# SCH_555-circuit_2025-10-18.net
KiCad netlist of a schematic drawn in EasyEDA
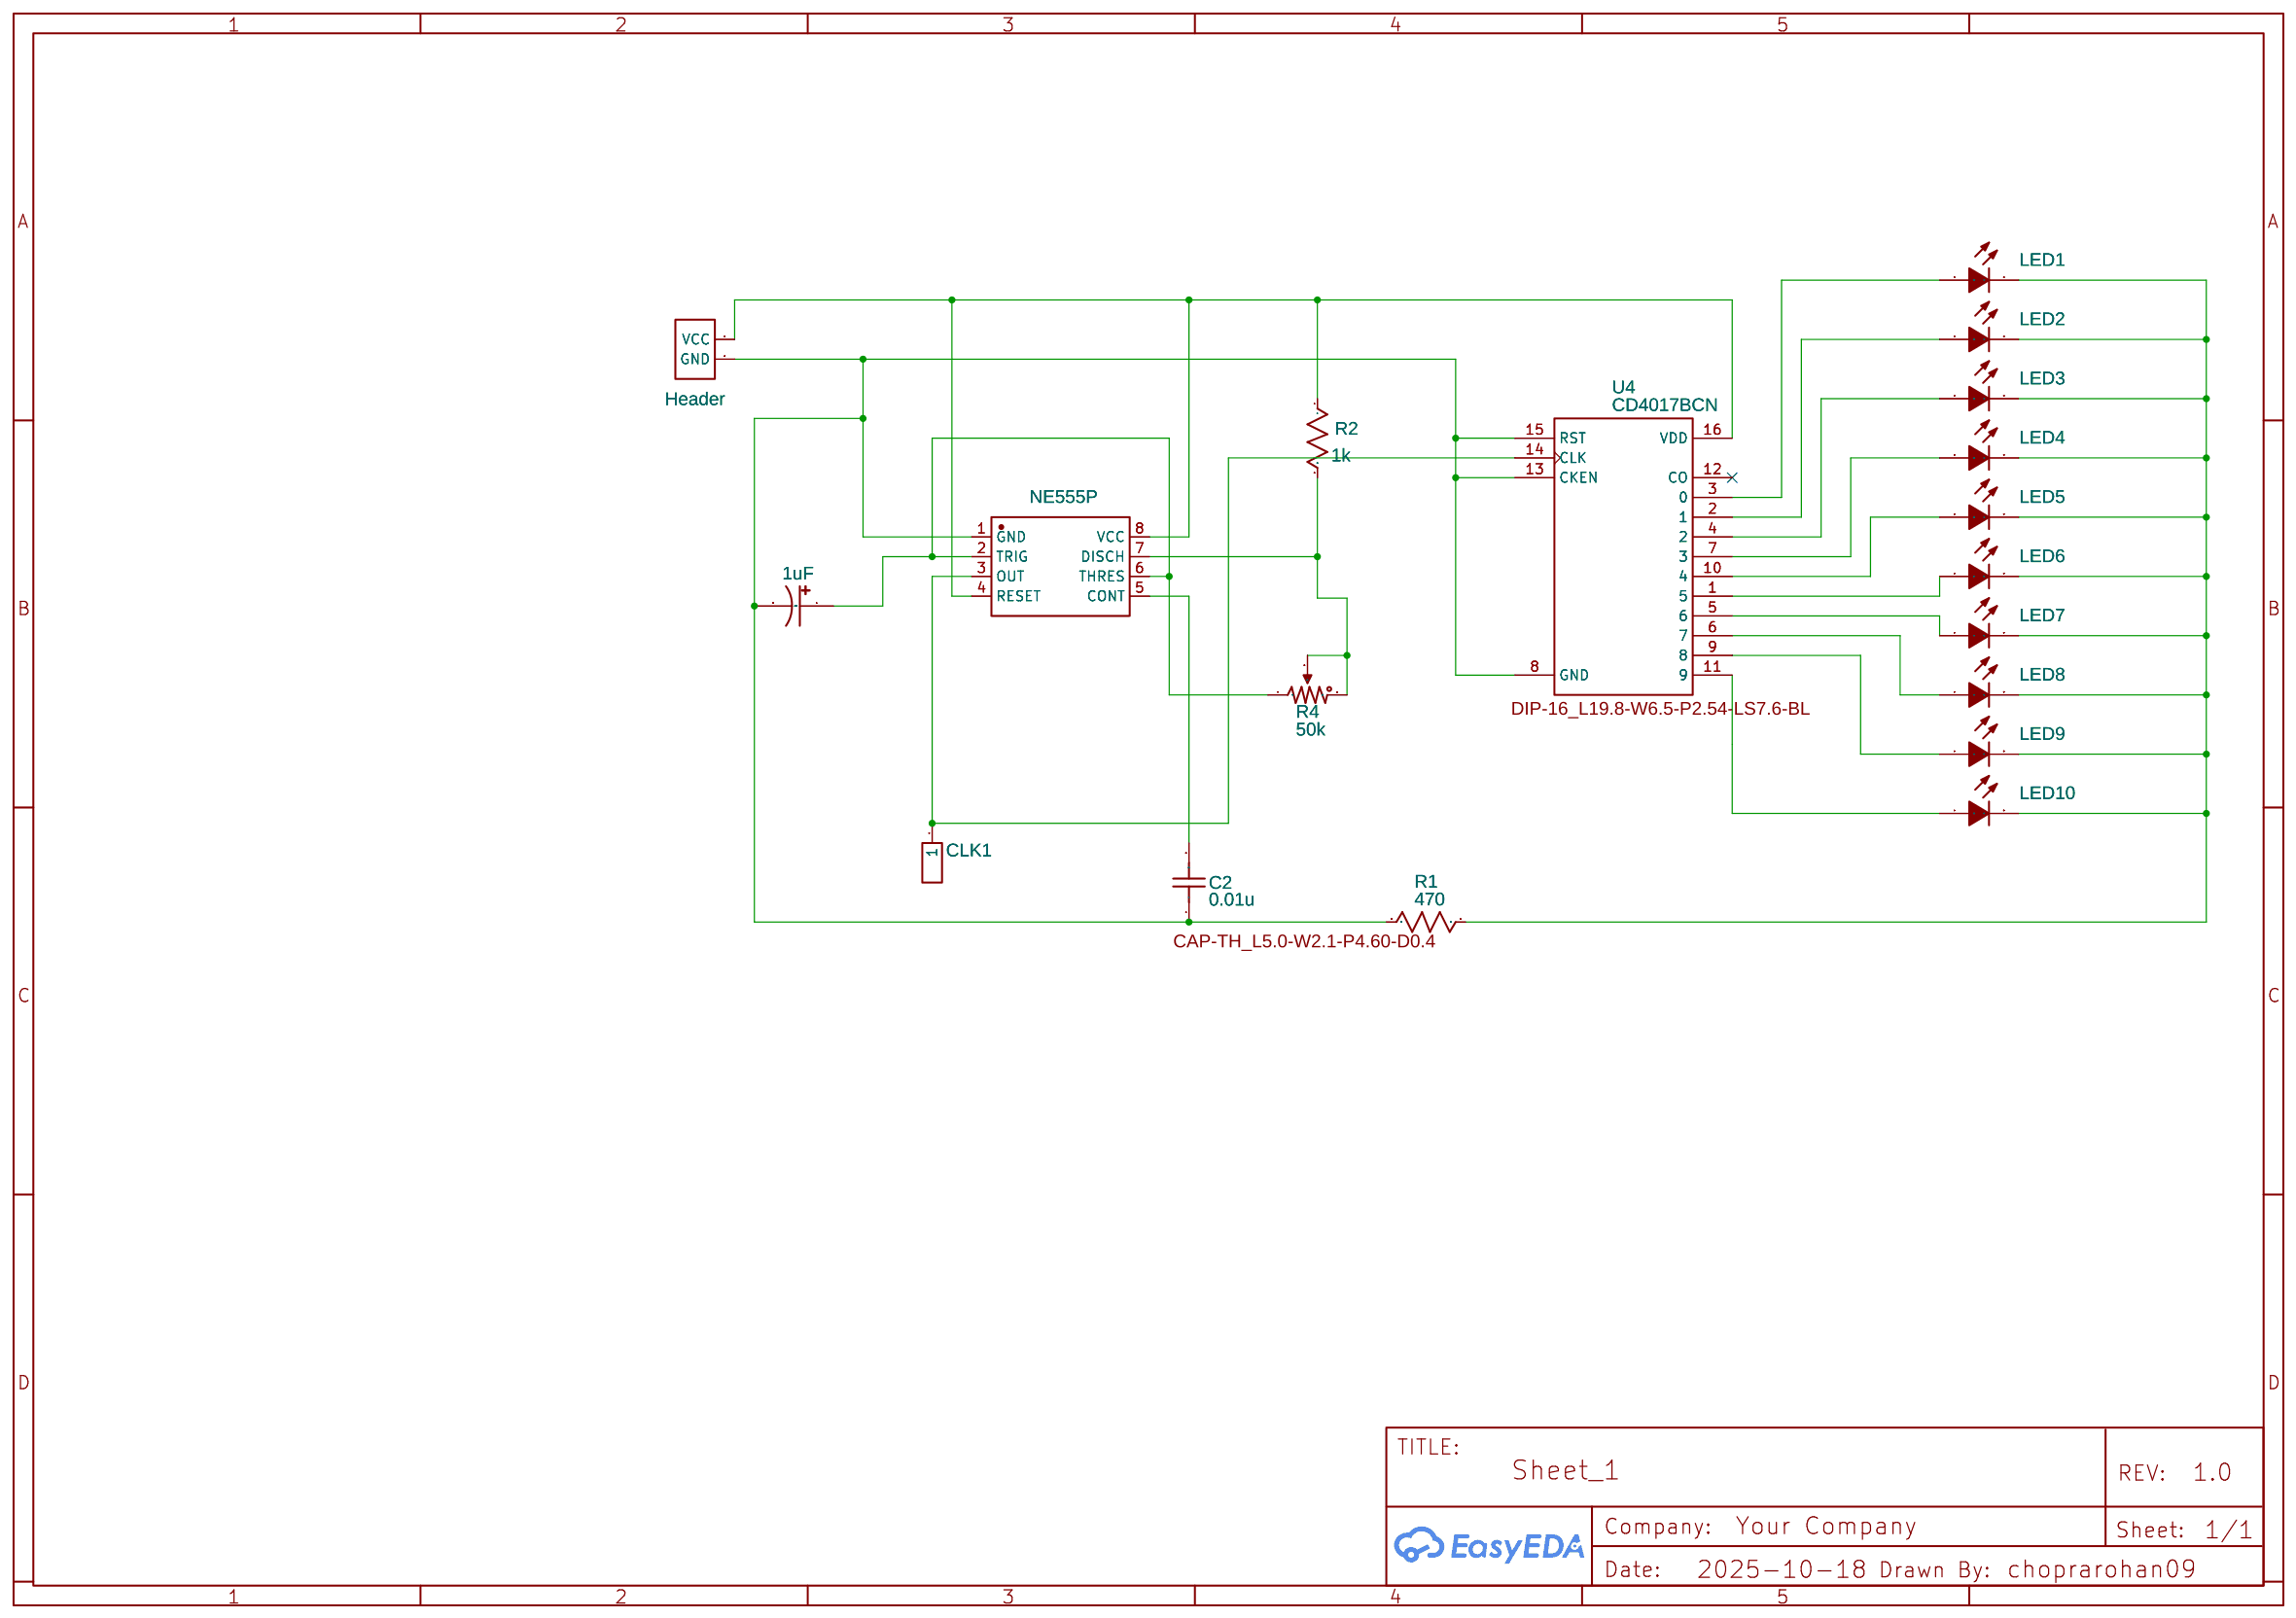
[diagram p0: schematic sheet]

(export (version "E")
  (design (tool "Eeschema 10.0.6"))
  (components
    (comp (ref "C1")
      (value "1uF")
      (fields (field (name "Manufacturer Part") "UVZ1H010MDD") (field (name "Manufacturer") "Nichicon(尼吉康)"))
      (libsource (lib "") (part "UVZ1H010MDD"))
    )
    (comp (ref "C2") (value "0.01u") (libsource (lib "") (part "C_0603_US")))
    (comp (ref "CLK1")
      (value "C81276")
      (fields
        (field (name "Manufacturer Part") "2.54-1*1P针")
        (field (name "Manufacturer") "BOOMELE(Boom Precision Elec)")
      )
      (libsource (lib "") (part "Header-Male-2.54_1x1"))
    )
    (comp (ref "H1") (value "Header") (libsource (lib "") (part "HEADER-FEMALE-2.54_1X2")))
    (comp (ref "LED1") (value "LED_5MM") (libsource (lib "") (part "LED_5MM")))
    (comp (ref "LED2") (value "LED_5MM") (libsource (lib "") (part "LED_5MM")))
    (comp (ref "LED3") (value "LED_5MM") (libsource (lib "") (part "LED_5MM")))
    (comp (ref "LED4") (value "LED_5MM") (libsource (lib "") (part "LED_5MM")))
    (comp (ref "LED5") (value "LED_5MM") (libsource (lib "") (part "LED_5MM")))
    (comp (ref "LED6") (value "LED_5MM") (libsource (lib "") (part "LED_5MM")))
    (comp (ref "LED7") (value "LED_5MM") (libsource (lib "") (part "LED_5MM")))
    (comp (ref "LED8") (value "LED_5MM") (libsource (lib "") (part "LED_5MM")))
    (comp (ref "LED9") (value "LED_5MM") (libsource (lib "") (part "LED_5MM")))
    (comp (ref "LED10") (value "LED_5MM") (libsource (lib "") (part "LED_5MM")))
    (comp (ref "R1")
      (value "470")
      (fields (field (name "Manufacturer Part") "?"))
      (libsource (lib "") (part "Resistor"))
    )
    (comp (ref "R2")
      (value "1k")
      (fields (field (name "Manufacturer Part") "?"))
      (libsource (lib "") (part "Resistor_1"))
    )
    (comp (ref "R4")
      (value "50k")
      (fields (field (name "Manufacturer Part") "?"))
      (libsource (lib "") (part "Potentiometer"))
    )
    (comp (ref "U2")
      (value "NE555P")
      (fields (field (name "Manufacturer") "TI(德州仪器)"))
      (libsource (lib "") (part "NE555P"))
    )
    (comp (ref "U4") (value "CD4017BCN") (libsource (lib "") (part "CD4017BCN")))
  )
  (nets
    (net (code "1") (name "Net-(H1-GND)") (class "Default")
      (node (ref "C1") (pin "2") (pinfunction "2_2") (pintype "unspecified"))
      (node (ref "C2") (pin "1") (pinfunction "1_1") (pintype "unspecified"))
      (node (ref "H1") (pin "2") (pinfunction "GND_2") (pintype "unspecified"))
      (node (ref "R1") (pin "2") (pinfunction "2_2") (pintype "unspecified"))
      (node (ref "U2") (pin "1") (pinfunction "GND_1") (pintype "unspecified"))
      (node (ref "U4") (pin "13") (pinfunction "CKEN_13") (pintype "unspecified"))
      (node (ref "U4") (pin "15") (pinfunction "RST_15") (pintype "unspecified"))
      (node (ref "U4") (pin "8") (pinfunction "GND_8") (pintype "passive"))
    )
    (net (code "2") (name "Net-(H1-VCC)") (class "Default")
      (node (ref "H1") (pin "1") (pinfunction "VCC_1") (pintype "unspecified"))
      (node (ref "R2") (pin "1") (pinfunction "1_1") (pintype "unspecified"))
      (node (ref "U2") (pin "4") (pinfunction "RESET_4") (pintype "unspecified"))
      (node (ref "U2") (pin "8") (pinfunction "VCC_8") (pintype "unspecified"))
      (node (ref "U4") (pin "16") (pinfunction "VDD_16") (pintype "passive"))
    )
    (net (code "3") (name "Net-(LED1-A)") (class "Default")
      (node (ref "LED1") (pin "1") (pinfunction "A_1") (pintype "input"))
      (node (ref "U4") (pin "3") (pinfunction "0_3") (pintype "output"))
    )
    (net (code "4") (name "Net-(LED1-K)") (class "Default")
      (node (ref "LED1") (pin "2") (pinfunction "K_2") (pintype "input"))
      (node (ref "LED10") (pin "2") (pinfunction "K_2") (pintype "input"))
      (node (ref "LED2") (pin "2") (pinfunction "K_2") (pintype "input"))
      (node (ref "LED3") (pin "2") (pinfunction "K_2") (pintype "input"))
      (node (ref "LED4") (pin "2") (pinfunction "K_2") (pintype "input"))
      (node (ref "LED5") (pin "2") (pinfunction "K_2") (pintype "input"))
      (node (ref "LED6") (pin "2") (pinfunction "K_2") (pintype "input"))
      (node (ref "LED7") (pin "2") (pinfunction "K_2") (pintype "input"))
      (node (ref "LED8") (pin "2") (pinfunction "K_2") (pintype "input"))
      (node (ref "LED9") (pin "2") (pinfunction "K_2") (pintype "input"))
      (node (ref "R1") (pin "1") (pinfunction "1_1") (pintype "unspecified"))
    )
    (net (code "5") (name "Net-(LED2-A)") (class "Default")
      (node (ref "LED2") (pin "1") (pinfunction "A_1") (pintype "input"))
      (node (ref "U4") (pin "2") (pinfunction "1_2") (pintype "output"))
    )
    (net (code "6") (name "Net-(LED3-A)") (class "Default")
      (node (ref "LED3") (pin "1") (pinfunction "A_1") (pintype "input"))
      (node (ref "U4") (pin "4") (pinfunction "2_4") (pintype "output"))
    )
    (net (code "7") (name "Net-(LED4-A)") (class "Default")
      (node (ref "LED4") (pin "1") (pinfunction "A_1") (pintype "input"))
      (node (ref "U4") (pin "7") (pinfunction "3_7") (pintype "output"))
    )
    (net (code "8") (name "Net-(LED5-A)") (class "Default")
      (node (ref "LED5") (pin "1") (pinfunction "A_1") (pintype "input"))
      (node (ref "U4") (pin "10") (pinfunction "4_10") (pintype "output"))
    )
    (net (code "9") (name "Net-(LED6-A)") (class "Default")
      (node (ref "LED6") (pin "1") (pinfunction "A_1") (pintype "input"))
      (node (ref "U4") (pin "1") (pinfunction "5_1") (pintype "output"))
    )
    (net (code "10") (name "Net-(LED7-A)") (class "Default")
      (node (ref "LED7") (pin "1") (pinfunction "A_1") (pintype "input"))
      (node (ref "U4") (pin "5") (pinfunction "6_5") (pintype "output"))
    )
    (net (code "11") (name "Net-(LED8-A)") (class "Default")
      (node (ref "LED8") (pin "1") (pinfunction "A_1") (pintype "input"))
      (node (ref "U4") (pin "6") (pinfunction "7_6") (pintype "output"))
    )
    (net (code "12") (name "Net-(LED9-A)") (class "Default")
      (node (ref "LED9") (pin "1") (pinfunction "A_1") (pintype "input"))
      (node (ref "U4") (pin "9") (pinfunction "8_9") (pintype "output"))
    )
    (net (code "13") (name "Net-(LED10-A)") (class "Default")
      (node (ref "LED10") (pin "1") (pinfunction "A_1") (pintype "input"))
      (node (ref "U4") (pin "11") (pinfunction "9_11") (pintype "output"))
    )
    (net (code "14") (name "Net-(R4-2)") (class "Default")
      (node (ref "R2") (pin "2") (pinfunction "2_2") (pintype "unspecified"))
      (node (ref "R4") (pin "2") (pinfunction "3_2") (pintype "unspecified"))
      (node (ref "R4") (pin "3") (pinfunction "2_3") (pintype "unspecified"))
      (node (ref "U2") (pin "7") (pinfunction "DISCH_7") (pintype "unspecified"))
    )
    (net (code "15") (name "Net-(U2-CONT)") (class "Default")
      (node (ref "C2") (pin "2") (pinfunction "2_2") (pintype "unspecified"))
      (node (ref "U2") (pin "5") (pinfunction "CONT_5") (pintype "unspecified"))
    )
    (net (code "16") (name "Net-(U2-OUT)") (class "Default")
      (node (ref "CLK1") (pin "1") (pinfunction "1_1") (pintype "unspecified"))
      (node (ref "U2") (pin "3") (pinfunction "OUT_3") (pintype "unspecified"))
      (node (ref "U4") (pin "14") (pinfunction "CLK_14") (pintype "unspecified"))
    )
    (net (code "17") (name "Net-(U2-THRES)") (class "Default")
      (node (ref "C1") (pin "1") (pinfunction "1_1") (pintype "unspecified"))
      (node (ref "R4") (pin "1") (pinfunction "1_1") (pintype "unspecified"))
      (node (ref "U2") (pin "2") (pinfunction "TRIG_2") (pintype "unspecified"))
      (node (ref "U2") (pin "6") (pinfunction "THRES_6") (pintype "unspecified"))
    )
    (net (code "18") (name "unconnected-(U4-CO-Pad12)") (class "Default")
      (node (ref "U4") (pin "12") (pinfunction "CO_12") (pintype "output+no_connect"))
    )
  )
)
